# MPPT_V1_0_1_Analog.net
KiCad netlist of a schematic drawn in Altium Designer
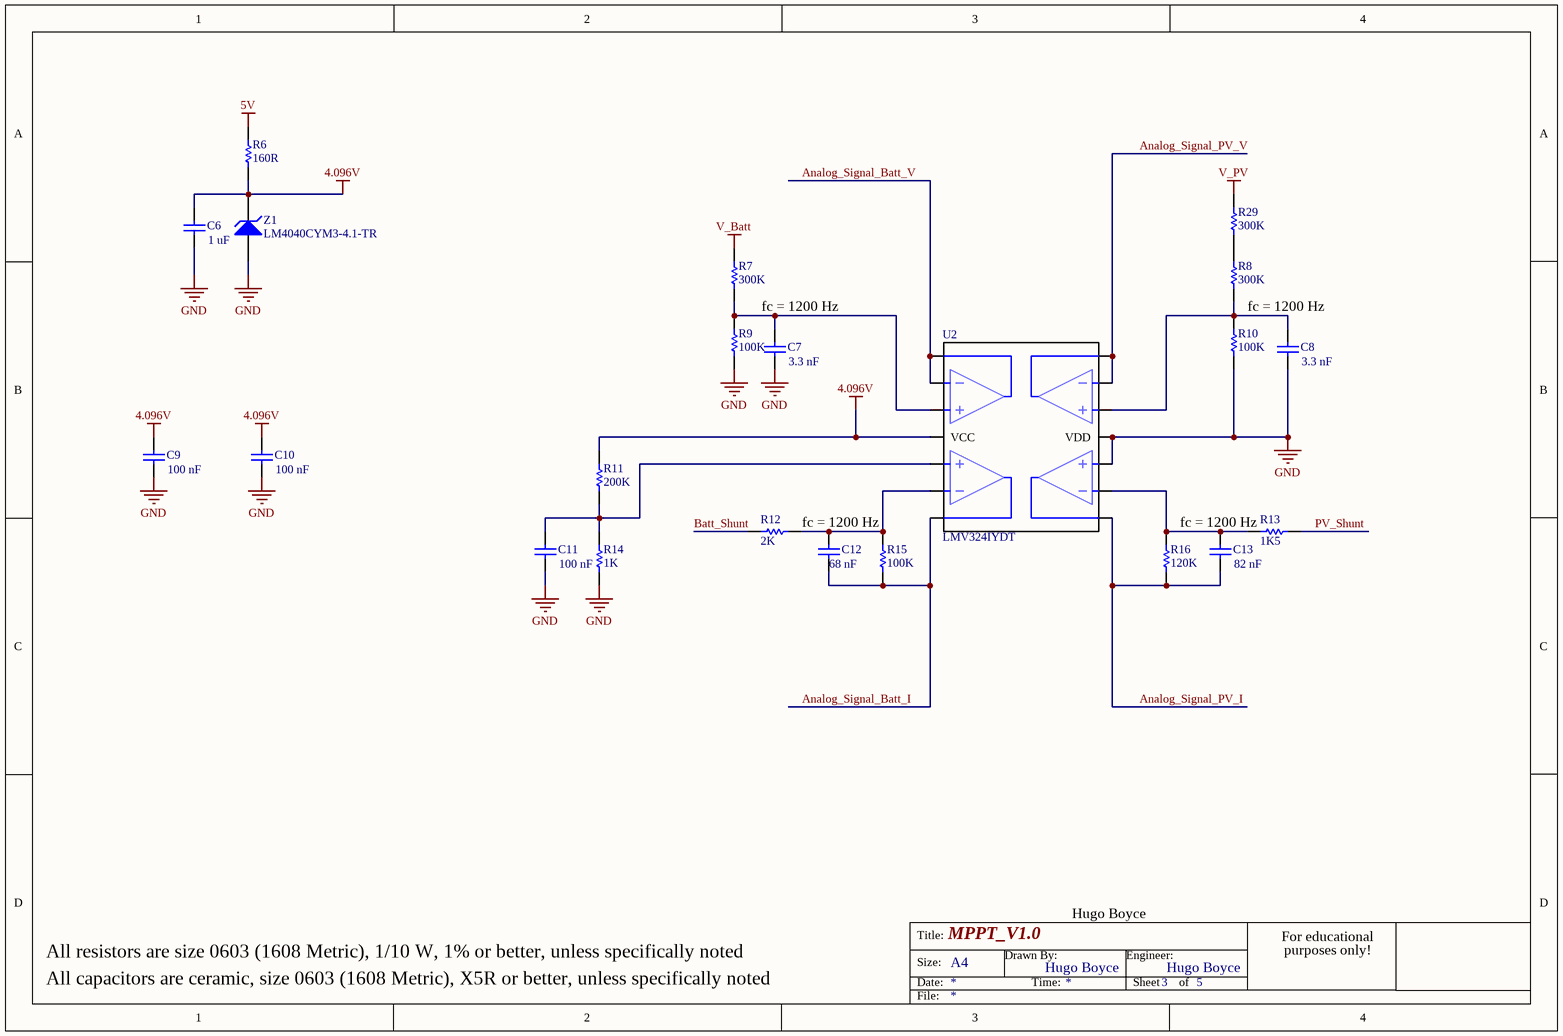
[diagram p0: MPPT_V1.0.1_Analog.SchDoc]

(export (version "E")
  (design (tool "Eeschema 10.0.6"))
  (components
    (comp (ref "C6")
      (value "1 uF")
      (footprint "CAPC1608N")
      (description "Capacitor")
      (fields (field (name "Comment") "Cap SMD") (field (name "PUBLISHER") "Altium Limited"))
      (libsource (lib "Miscellaneous Devices") (part "Cap SMD"))
    )
    (comp (ref "C7")
      (value "3.3 nF")
      (footprint "CAPC1608N")
      (description "Capacitor")
      (fields (field (name "Comment") "Cap SMD") (field (name "PUBLISHER") "Altium Limited"))
      (libsource (lib "Miscellaneous Devices") (part "Cap SMD"))
    )
    (comp (ref "C8")
      (value "3.3 nF")
      (footprint "CAPC1608N")
      (description "Capacitor")
      (fields (field (name "Comment") "Cap SMD") (field (name "PUBLISHER") "Altium Limited"))
      (libsource (lib "Miscellaneous Devices") (part "Cap SMD"))
    )
    (comp (ref "C9")
      (value "100 nF")
      (footprint "CAPC1608N")
      (description "Capacitor")
      (fields (field (name "Comment") "Cap SMD") (field (name "PUBLISHER") "Altium Limited"))
      (libsource (lib "Miscellaneous Devices") (part "Cap SMD"))
    )
    (comp (ref "C10")
      (value "100 nF")
      (footprint "CAPC1608N")
      (description "Capacitor")
      (fields (field (name "Comment") "Cap SMD") (field (name "PUBLISHER") "Altium Limited"))
      (libsource (lib "Miscellaneous Devices") (part "Cap SMD"))
    )
    (comp (ref "C11")
      (value "100 nF")
      (footprint "CAPC1608N")
      (description "Capacitor")
      (fields (field (name "Comment") "Cap SMD") (field (name "PUBLISHER") "Altium Limited"))
      (libsource (lib "Miscellaneous Devices") (part "Cap SMD"))
    )
    (comp (ref "C12")
      (value "68 nF")
      (footprint "CAPC1608N")
      (description "Capacitor")
      (fields (field (name "Comment") "Cap SMD") (field (name "PUBLISHER") "Altium Limited"))
      (libsource (lib "Miscellaneous Devices") (part "Cap SMD"))
    )
    (comp (ref "C13")
      (value "82 nF")
      (footprint "CAPC1608N")
      (description "Capacitor")
      (fields (field (name "Comment") "Cap SMD") (field (name "PUBLISHER") "Altium Limited"))
      (libsource (lib "Miscellaneous Devices") (part "Cap SMD"))
    )
    (comp (ref "R6")
      (value "160R")
      (footprint "RESC1608N")
      (description "Resistor")
      (fields (field (name "Comment") "Res SMD") (field (name "PUBLISHER") "Altium Limited"))
      (libsource (lib "Miscellaneous Devices") (part "Res SMD"))
    )
    (comp (ref "R7")
      (value "300K")
      (footprint "RESC1608N")
      (description "Resistor")
      (fields (field (name "Comment") "Res SMD") (field (name "PUBLISHER") "Altium Limited"))
      (libsource (lib "Miscellaneous Devices") (part "Res SMD"))
    )
    (comp (ref "R8")
      (value "300K")
      (footprint "RESC1608N")
      (description "Resistor")
      (fields (field (name "Comment") "Res SMD") (field (name "PUBLISHER") "Altium Limited"))
      (libsource (lib "Miscellaneous Devices") (part "Res SMD"))
    )
    (comp (ref "R9")
      (value "100K")
      (footprint "RESC1608N")
      (description "Resistor")
      (fields (field (name "Comment") "Res SMD") (field (name "PUBLISHER") "Altium Limited"))
      (libsource (lib "Miscellaneous Devices") (part "Res SMD"))
    )
    (comp (ref "R10")
      (value "100K")
      (footprint "RESC1608N")
      (description "Resistor")
      (fields (field (name "Comment") "Res SMD") (field (name "PUBLISHER") "Altium Limited"))
      (libsource (lib "Miscellaneous Devices") (part "Res SMD"))
    )
    (comp (ref "R11")
      (value "200K")
      (footprint "RESC1608N")
      (description "Resistor")
      (fields (field (name "Comment") "Res SMD") (field (name "PUBLISHER") "Altium Limited"))
      (libsource (lib "Miscellaneous Devices") (part "Res SMD"))
    )
    (comp (ref "R12")
      (value "2K")
      (footprint "RESC1608N")
      (description "Resistor")
      (fields (field (name "Comment") "Res SMD") (field (name "PUBLISHER") "Altium Limited"))
      (libsource (lib "Miscellaneous Devices") (part "Res SMD"))
    )
    (comp (ref "R13")
      (value "1K5")
      (footprint "RESC1608N")
      (description "Resistor")
      (fields (field (name "Comment") "Res SMD") (field (name "PUBLISHER") "Altium Limited"))
      (libsource (lib "Miscellaneous Devices") (part "Res SMD"))
    )
    (comp (ref "R14")
      (value "1K")
      (footprint "RESC1608N")
      (description "Resistor")
      (fields (field (name "Comment") "Res SMD") (field (name "PUBLISHER") "Altium Limited"))
      (libsource (lib "Miscellaneous Devices") (part "Res SMD"))
    )
    (comp (ref "R15")
      (value "100K")
      (footprint "RESC1608N")
      (description "Resistor")
      (fields (field (name "Comment") "Res SMD") (field (name "PUBLISHER") "Altium Limited"))
      (libsource (lib "Miscellaneous Devices") (part "Res SMD"))
    )
    (comp (ref "R16")
      (value "120K")
      (footprint "RESC1608N")
      (description "Resistor")
      (fields (field (name "Comment") "Res SMD") (field (name "PUBLISHER") "Altium Limited"))
      (libsource (lib "Miscellaneous Devices") (part "Res SMD"))
    )
    (comp (ref "R29")
      (value "300K")
      (footprint "RESC1608N")
      (description "Resistor")
      (fields (field (name "Comment") "Res SMD") (field (name "PUBLISHER") "Altium Limited"))
      (libsource (lib "Miscellaneous Devices") (part "Res SMD"))
    )
    (comp (ref "U2")
      (value "LMV324IYDT")
      (footprint "LMV324IYDT")
      (description "IC OPAMP GP 1.3MHZ RRO 14SO")
      (fields
        (field (name "MANUFACTURER") "STMicroelectronics")
        (field (name "BASE PART NUMBER") "LMV324")
        (field (name "MANUFACTURER PART NUMBER") "LMV324IYDT")
      )
      (libsource (lib "MPPT_SCH_Library") (part "LMV324IYDT"))
    )
    (comp (ref "Z1")
      (value "LM4040CYM3-4.1-TR")
      (footprint "LM4040C")
      (description "IC VREF SHUNT 4.096V SOT23")
      (fields
        (field (name "MANUFACTURER") "Microchip Technology")
        (field (name "TOLERANCE") "±0.5%")
        (field (name "MANUFACTURER PART NUMBER") "LM4040CYM3-4.1-TR")
      )
      (libsource (lib "MPPT_SCH_Library") (part "LM4040CYM3-4.1-TR"))
    )
  )
  (nets
    (net (code "1") (name "/Analog_Signal_Batt_I") (class "Default")
      (node (ref "C12") (pin "1") (pinfunction "1_1") (pintype "passive"))
      (node (ref "R15") (pin "1") (pinfunction "1_1") (pintype "passive"))
      (node (ref "U2") (pin "7") (pinfunction "OUT_2_7") (pintype "passive"))
    )
    (net (code "2") (name "/Analog_Signal_Batt_V") (class "Default")
      (node (ref "U2") (pin "1") (pinfunction "OUT1_1") (pintype "passive"))
      (node (ref "U2") (pin "2") (pinfunction "IN-_1_2") (pintype "passive"))
    )
    (net (code "3") (name "/Analog_Signal_PV_I") (class "Default")
      (node (ref "C13") (pin "1") (pinfunction "1_1") (pintype "passive"))
      (node (ref "R16") (pin "1") (pinfunction "1_1") (pintype "passive"))
      (node (ref "U2") (pin "8") (pinfunction "OUT_3_8") (pintype "passive"))
    )
    (net (code "4") (name "/Analog_Signal_PV_V") (class "Default")
      (node (ref "U2") (pin "13") (pinfunction "IN-_4_13") (pintype "passive"))
      (node (ref "U2") (pin "14") (pinfunction "OUT_4_14") (pintype "passive"))
    )
    (net (code "5") (name "/Batt_Shunt") (class "Default")
      (node (ref "R12") (pin "1") (pinfunction "1_1") (pintype "passive"))
    )
    (net (code "6") (name "/PV_Shunt") (class "Default")
      (node (ref "R13") (pin "2") (pinfunction "2_2") (pintype "passive"))
    )
    (net (code "7") (name "4.096V") (class "Default")
      (node (ref "C10") (pin "2") (pinfunction "2_2") (pintype "passive"))
      (node (ref "C6") (pin "2") (pinfunction "2_2") (pintype "passive"))
      (node (ref "C9") (pin "2") (pinfunction "2_2") (pintype "passive"))
      (node (ref "R11") (pin "2") (pinfunction "2_2") (pintype "passive"))
      (node (ref "R6") (pin "1") (pinfunction "1_1") (pintype "passive"))
      (node (ref "U2") (pin "4") (pinfunction "VCC_4") (pintype "passive"))
      (node (ref "Z1") (pin "1") (pinfunction "K_1") (pintype "passive"))
    )
    (net (code "8") (name "5V") (class "Default")
      (node (ref "R6") (pin "2") (pinfunction "2_2") (pintype "passive"))
    )
    (net (code "9") (name "GND") (class "Default")
      (node (ref "C10") (pin "1") (pinfunction "1_1") (pintype "passive"))
      (node (ref "C11") (pin "1") (pinfunction "1_1") (pintype "passive"))
      (node (ref "C6") (pin "1") (pinfunction "1_1") (pintype "passive"))
      (node (ref "C7") (pin "1") (pinfunction "1_1") (pintype "passive"))
      (node (ref "C8") (pin "1") (pinfunction "1_1") (pintype "passive"))
      (node (ref "C9") (pin "1") (pinfunction "1_1") (pintype "passive"))
      (node (ref "R10") (pin "1") (pinfunction "1_1") (pintype "passive"))
      (node (ref "R14") (pin "1") (pinfunction "1_1") (pintype "passive"))
      (node (ref "R9") (pin "1") (pinfunction "1_1") (pintype "passive"))
      (node (ref "U2") (pin "10") (pinfunction "IN+_3_10") (pintype "passive"))
      (node (ref "U2") (pin "11") (pinfunction "VDD_11") (pintype "passive"))
      (node (ref "Z1") (pin "2") (pinfunction "A_2") (pintype "passive"))
    )
    (net (code "10") (name "Net-(R29-Pad1)") (class "Default")
      (node (ref "R29") (pin "1") (pinfunction "1_1") (pintype "passive"))
      (node (ref "R8") (pin "2") (pinfunction "2_2") (pintype "passive"))
    )
    (net (code "11") (name "Net-(U2-IN+_1)") (class "Default")
      (node (ref "C7") (pin "2") (pinfunction "2_2") (pintype "passive"))
      (node (ref "R7") (pin "1") (pinfunction "1_1") (pintype "passive"))
      (node (ref "R9") (pin "2") (pinfunction "2_2") (pintype "passive"))
      (node (ref "U2") (pin "3") (pinfunction "IN+_1_3") (pintype "passive"))
    )
    (net (code "12") (name "Net-(U2-IN+_2)") (class "Default")
      (node (ref "C12") (pin "2") (pinfunction "2_2") (pintype "passive"))
      (node (ref "R12") (pin "2") (pinfunction "2_2") (pintype "passive"))
      (node (ref "R15") (pin "2") (pinfunction "2_2") (pintype "passive"))
      (node (ref "U2") (pin "6") (pinfunction "IN+_2_6") (pintype "passive"))
    )
    (net (code "13") (name "Net-(U2-IN+_4)") (class "Default")
      (node (ref "C8") (pin "2") (pinfunction "2_2") (pintype "passive"))
      (node (ref "R10") (pin "2") (pinfunction "2_2") (pintype "passive"))
      (node (ref "R8") (pin "1") (pinfunction "1_1") (pintype "passive"))
      (node (ref "U2") (pin "12") (pinfunction "IN+_4_12") (pintype "passive"))
    )
    (net (code "14") (name "Net-(U2-IN-_2)") (class "Default")
      (node (ref "C11") (pin "2") (pinfunction "2_2") (pintype "passive"))
      (node (ref "R11") (pin "1") (pinfunction "1_1") (pintype "passive"))
      (node (ref "R14") (pin "2") (pinfunction "2_2") (pintype "passive"))
      (node (ref "U2") (pin "5") (pinfunction "IN-_2_5") (pintype "passive"))
    )
    (net (code "15") (name "Net-(U2-IN-_3)") (class "Default")
      (node (ref "C13") (pin "2") (pinfunction "2_2") (pintype "passive"))
      (node (ref "R13") (pin "1") (pinfunction "1_1") (pintype "passive"))
      (node (ref "R16") (pin "2") (pinfunction "2_2") (pintype "passive"))
      (node (ref "U2") (pin "9") (pinfunction "IN-_3_9") (pintype "passive"))
    )
    (net (code "16") (name "V_Batt") (class "Default")
      (node (ref "R7") (pin "2") (pinfunction "2_2") (pintype "passive"))
    )
    (net (code "17") (name "V_PV") (class "Default")
      (node (ref "R29") (pin "2") (pinfunction "2_2") (pintype "passive"))
    )
  )
)
